# OpenBook_Reader_Schematic_Final.net
KiCad netlist of a schematic drawn in EAGLE
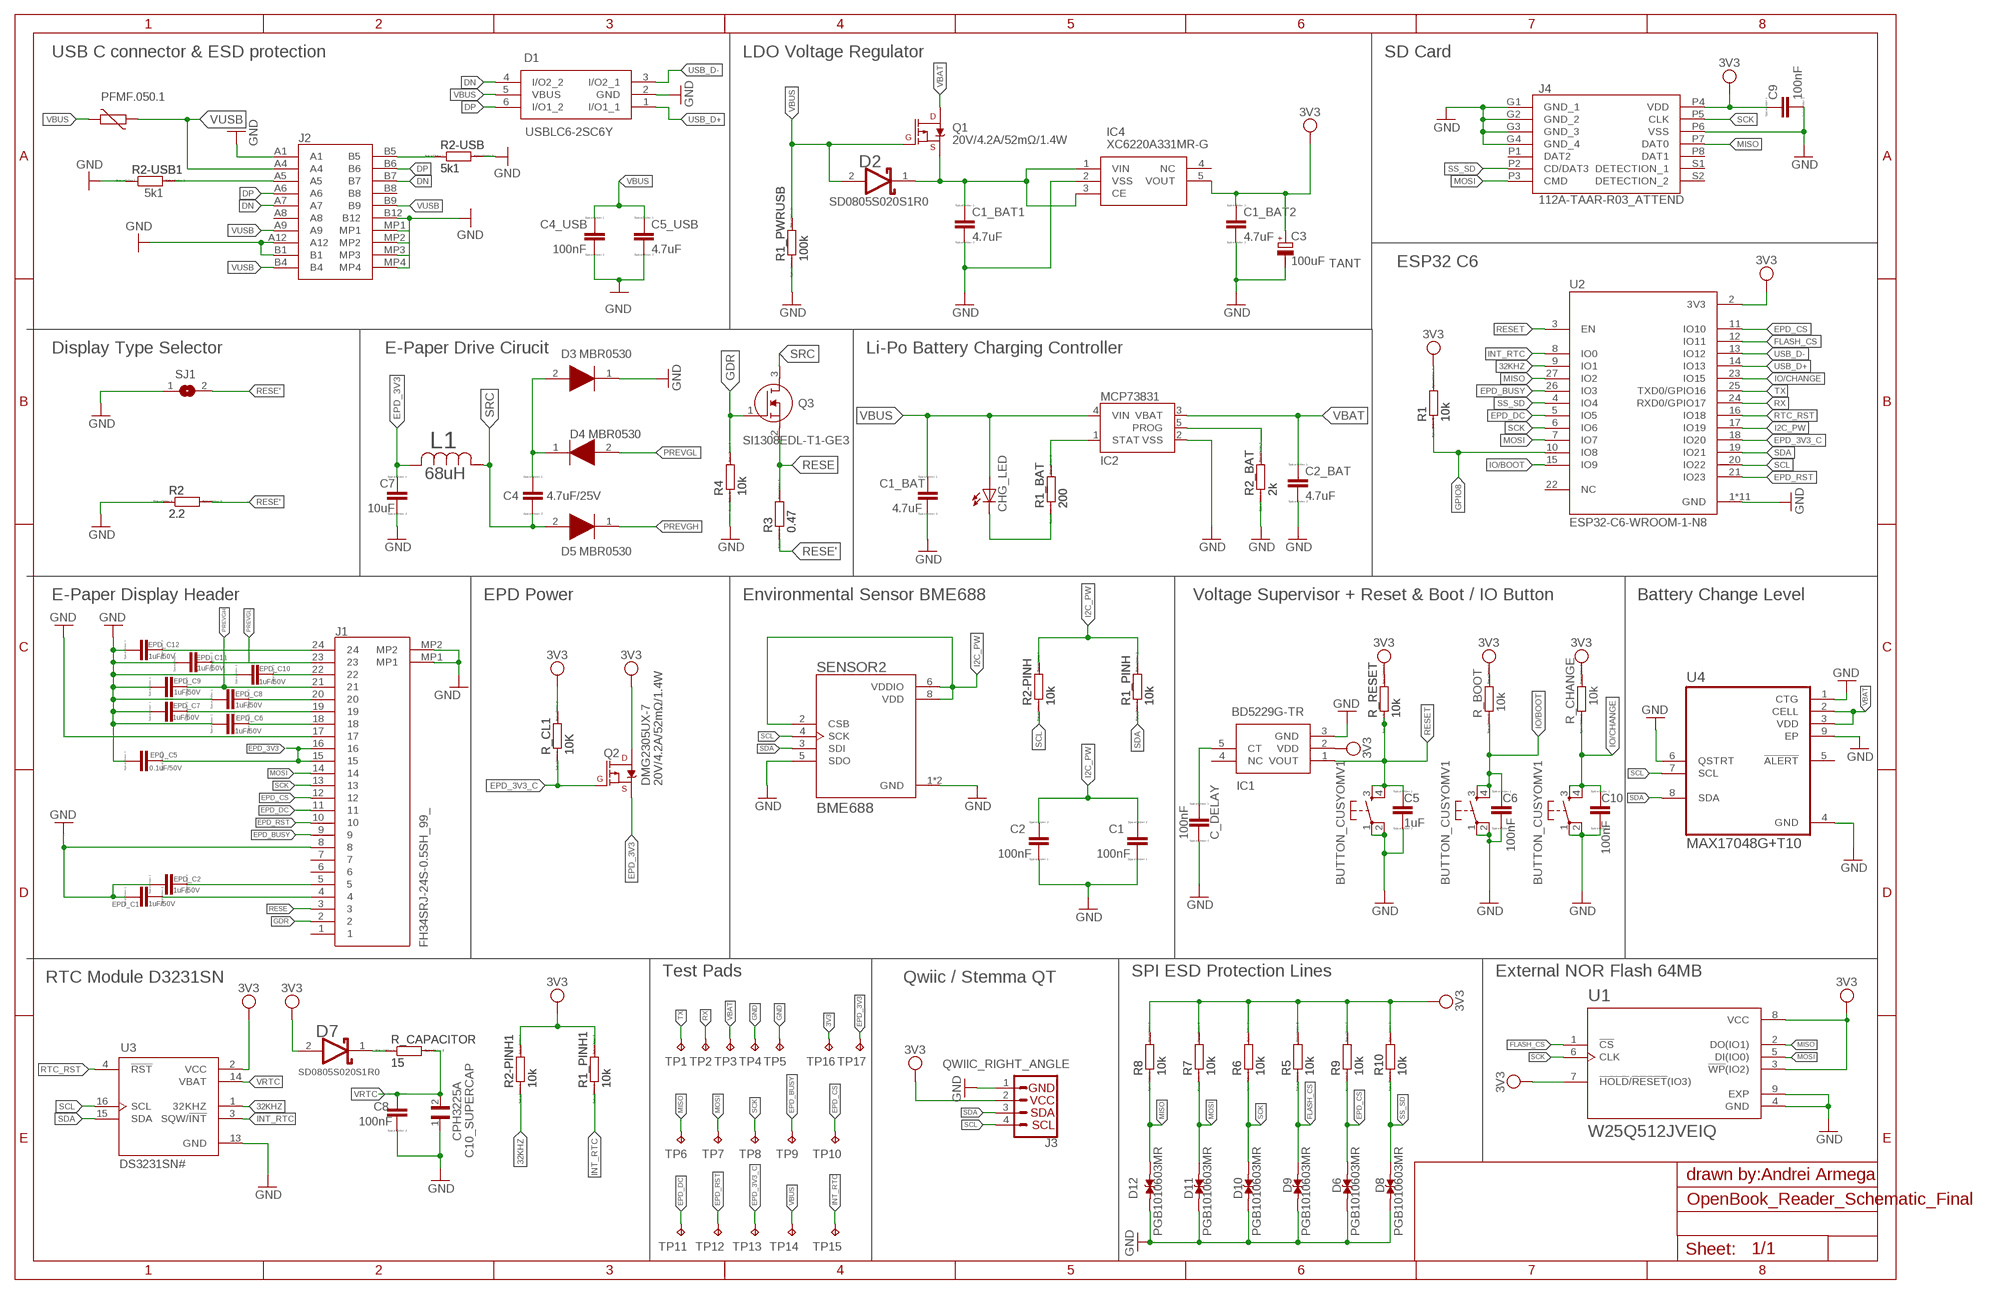
[diagram p0: schematic, sheet 1]

(export (version "E")
  (design (tool "Eeschema 10.0.6"))
  (components
    (comp (ref "BUT1")
      (value "BUTTON_CUSYOMV1")
      (footprint "eagle-import:MYBUTTON")
      (libsource (lib "eagle-import") (part "BUTTON_CUSYOMV1"))
    )
    (comp (ref "BUT2")
      (value "BUTTON_CUSYOMV1")
      (footprint "eagle-import:MYBUTTON")
      (libsource (lib "eagle-import") (part "BUTTON_CUSYOMV1"))
    )
    (comp (ref "BUT3")
      (value "BUTTON_CUSYOMV1")
      (footprint "eagle-import:MYBUTTON")
      (libsource (lib "eagle-import") (part "BUTTON_CUSYOMV1"))
    )
    (comp (ref "C1")
      (value "100nF")
      (footprint "eagle-import:ESP32_WROVER_EAGLE-LTSPICE_C0402")
      (libsource (lib "eagle-import") (part "ESP32_WROVER_EAGLE-LTSPICE_CC0402"))
    )
    (comp (ref "C1_BAT")
      (value "4.7uF")
      (footprint "eagle-import:ESP32_WROVER_EAGLE-LTSPICE_C0402")
      (libsource (lib "eagle-import") (part "ESP32_WROVER_EAGLE-LTSPICE_CC0402"))
    )
    (comp (ref "C1_BAT1")
      (value "4.7uF")
      (footprint "eagle-import:ESP32_WROVER_EAGLE-LTSPICE_C0402")
      (libsource (lib "eagle-import") (part "ESP32_WROVER_EAGLE-LTSPICE_CC0402"))
    )
    (comp (ref "C1_BAT2")
      (value "4.7uF")
      (footprint "eagle-import:ESP32_WROVER_EAGLE-LTSPICE_C0402")
      (libsource (lib "eagle-import") (part "ESP32_WROVER_EAGLE-LTSPICE_CC0402"))
    )
    (comp (ref "C2")
      (value "100nF")
      (footprint "eagle-import:ESP32_WROVER_EAGLE-LTSPICE_C0402")
      (libsource (lib "eagle-import") (part "ESP32_WROVER_EAGLE-LTSPICE_CC0402"))
    )
    (comp (ref "C2_BAT")
      (value "4.7uF")
      (footprint "eagle-import:ESP32_WROVER_EAGLE-LTSPICE_C0402")
      (libsource (lib "eagle-import") (part "ESP32_WROVER_EAGLE-LTSPICE_CC0402"))
    )
    (comp (ref "C3")
      (value "100uF")
      (footprint "eagle-import:RCL_CT3528")
      (libsource (lib "eagle-import") (part "RCL_CPOL-EUCT3528"))
    )
    (comp (ref "C4")
      (value "4.7uF/25V")
      (footprint "eagle-import:ESP32_WROVER_EAGLE-LTSPICE_C0402")
      (libsource (lib "eagle-import") (part "ESP32_WROVER_EAGLE-LTSPICE_CC0402"))
    )
    (comp (ref "C4_USB")
      (value "100nF")
      (footprint "eagle-import:ESP32_WROVER_EAGLE-LTSPICE_C0402")
      (libsource (lib "eagle-import") (part "ESP32_WROVER_EAGLE-LTSPICE_CC0402"))
    )
    (comp (ref "C5")
      (value "1uF")
      (footprint "eagle-import:ESP32_WROVER_EAGLE-LTSPICE_C0402")
      (libsource (lib "eagle-import") (part "EAGLE-LTSPICE_CC0402"))
    )
    (comp (ref "C5_USB")
      (value "4.7uF")
      (footprint "eagle-import:ESP32_WROVER_EAGLE-LTSPICE_C0402")
      (libsource (lib "eagle-import") (part "ESP32_WROVER_EAGLE-LTSPICE_CC0402"))
    )
    (comp (ref "C6")
      (value "100nF")
      (footprint "eagle-import:ESP32_WROVER_EAGLE-LTSPICE_C0402")
      (libsource (lib "eagle-import") (part "EAGLE-LTSPICE_CC0402"))
    )
    (comp (ref "C7")
      (value "10uF")
      (footprint "eagle-import:ESP32_WROVER_EAGLE-LTSPICE_C0402")
      (libsource (lib "eagle-import") (part "ESP32_WROVER_EAGLE-LTSPICE_CC0402"))
    )
    (comp (ref "C8")
      (value "100nF")
      (footprint "eagle-import:ESP32_WROVER_EAGLE-LTSPICE_C0402")
      (libsource (lib "eagle-import") (part "EAGLE-LTSPICE_CC0402"))
    )
    (comp (ref "C9")
      (value "100nF")
      (footprint "eagle-import:ESP32_WROVER_EAGLE-LTSPICE_C0402")
      (libsource (lib "eagle-import") (part "EAGLE-LTSPICE_CC0402"))
    )
    (comp (ref "C10")
      (value "100nF")
      (footprint "eagle-import:ESP32_WROVER_EAGLE-LTSPICE_C0402")
      (libsource (lib "eagle-import") (part "EAGLE-LTSPICE_CC0402"))
    )
    (comp (ref "C10_SUPERCAP")
      (value "CPH3225A")
      (footprint "eagle-import:CAPCP3225X100N")
      (fields (field (name "MF") "Seiko Instruments"))
      (libsource (lib "eagle-import") (part "CPH3225A"))
    )
    (comp (ref "CHG_LED")
      (value "ADAFRUIT_LEDCHIP-LED0603")
      (footprint "eagle-import:ADAFRUIT_CHIP-LED0603")
      (libsource (lib "eagle-import") (part "ADAFRUIT_LEDCHIP-LED0603"))
    )
    (comp (ref "C_DELAY")
      (value "100nF")
      (footprint "eagle-import:ESP32_WROVER_EAGLE-LTSPICE_C0402")
      (libsource (lib "eagle-import") (part "EAGLE-LTSPICE_CC0402"))
    )
    (comp (ref "D1")
      (value "USBLC6-2SC6Y")
      (footprint "eagle-import:SOT95P280X145-6N")
      (fields (field (name "MF") "STMicroelectronics"))
      (libsource (lib "eagle-import") (part "USBLC6-2SC6Y"))
    )
    (comp (ref "D2")
      (value "ESP32_WROVER_AVX---SD0805S020S1R0_AVX_SD0805S020S1R0_0_0AVX_SD0805S020S1R0_0_0")
      (footprint "eagle-import:ESP32_WROVER_AVX---SD0805S020S1R0_AVX_SD0805S020S1R0_0")
      (fields
        (field (name "DIGIKEY_PART_NUMBER") "478-7800-1-ND")
        (field (name "MF") "AVX")
        (field (name "MOUSER_PART_NUMBER") "581-SD0805S020S1R0")
      )
      (libsource (lib "eagle-import") (part "ESP32_WROVER_AVX---SD0805S020S1R0_AVX_SD0805S020S1R0_0_0AVX_SD0805S020S1R0_0_0"))
    )
    (comp (ref "D3")
      (value "MBR0530")
      (footprint "eagle-import:SOD3716X135N")
      (fields (field (name "MF") "ON Semiconductor"))
      (libsource (lib "eagle-import") (part "MBR0530"))
    )
    (comp (ref "D4")
      (value "MBR0530")
      (footprint "eagle-import:SOD3716X135N")
      (fields (field (name "MF") "ON Semiconductor"))
      (libsource (lib "eagle-import") (part "MBR0530"))
    )
    (comp (ref "D5")
      (value "MBR0530")
      (footprint "eagle-import:SOD3716X135N")
      (fields (field (name "MF") "ON Semiconductor"))
      (libsource (lib "eagle-import") (part "MBR0530"))
    )
    (comp (ref "D6")
      (value "PGB1010603MR")
      (footprint "eagle-import:DIOC1608X36N")
      (fields (field (name "MF") "Littelfuse Inc."))
      (libsource (lib "eagle-import") (part "PGB1010603MR"))
    )
    (comp (ref "D7")
      (value "ESP32_WROVER_AVX---SD0805S020S1R0_AVX_SD0805S020S1R0_0_0AVX_SD0805S020S1R0_0_0")
      (footprint "eagle-import:ESP32_WROVER_AVX---SD0805S020S1R0_AVX_SD0805S020S1R0_0")
      (fields
        (field (name "DIGIKEY_PART_NUMBER") "478-7800-1-ND")
        (field (name "MF") "AVX")
        (field (name "MOUSER_PART_NUMBER") "581-SD0805S020S1R0")
      )
      (libsource (lib "eagle-import") (part "ESP32_WROVER_AVX---SD0805S020S1R0_AVX_SD0805S020S1R0_0_0AVX_SD0805S020S1R0_0_0"))
    )
    (comp (ref "D8")
      (value "PGB1010603MR")
      (footprint "eagle-import:DIOC1608X36N")
      (fields (field (name "MF") "Littelfuse Inc."))
      (libsource (lib "eagle-import") (part "PGB1010603MR"))
    )
    (comp (ref "D9")
      (value "PGB1010603MR")
      (footprint "eagle-import:DIOC1608X36N")
      (fields (field (name "MF") "Littelfuse Inc."))
      (libsource (lib "eagle-import") (part "PGB1010603MR"))
    )
    (comp (ref "D10")
      (value "PGB1010603MR")
      (footprint "eagle-import:DIOC1608X36N")
      (fields (field (name "MF") "Littelfuse Inc."))
      (libsource (lib "eagle-import") (part "PGB1010603MR"))
    )
    (comp (ref "D11")
      (value "PGB1010603MR")
      (footprint "eagle-import:DIOC1608X36N")
      (fields (field (name "MF") "Littelfuse Inc."))
      (libsource (lib "eagle-import") (part "PGB1010603MR"))
    )
    (comp (ref "D12")
      (value "PGB1010603MR")
      (footprint "eagle-import:DIOC1608X36N")
      (fields (field (name "MF") "Littelfuse Inc."))
      (libsource (lib "eagle-import") (part "PGB1010603MR"))
    )
    (comp (ref "EPD_C1")
      (value "1uF/50V")
      (footprint "eagle-import:ESP32_WROVER_EAGLE-LTSPICE_C0402")
      (libsource (lib "eagle-import") (part "ESP32_WROVER_EAGLE-LTSPICE_CC0402"))
    )
    (comp (ref "EPD_C2")
      (value "1uF/50V")
      (footprint "eagle-import:ESP32_WROVER_EAGLE-LTSPICE_C0402")
      (libsource (lib "eagle-import") (part "ESP32_WROVER_EAGLE-LTSPICE_CC0402"))
    )
    (comp (ref "EPD_C5")
      (value "0.1uF/50V")
      (footprint "eagle-import:ESP32_WROVER_EAGLE-LTSPICE_C0402")
      (libsource (lib "eagle-import") (part "ESP32_WROVER_EAGLE-LTSPICE_CC0402"))
    )
    (comp (ref "EPD_C6")
      (value "1uF/50V")
      (footprint "eagle-import:ESP32_WROVER_EAGLE-LTSPICE_C0402")
      (libsource (lib "eagle-import") (part "ESP32_WROVER_EAGLE-LTSPICE_CC0402"))
    )
    (comp (ref "EPD_C7")
      (value "1uF/50V")
      (footprint "eagle-import:ESP32_WROVER_EAGLE-LTSPICE_C0402")
      (libsource (lib "eagle-import") (part "ESP32_WROVER_EAGLE-LTSPICE_CC0402"))
    )
    (comp (ref "EPD_C8")
      (value "1uF/50V")
      (footprint "eagle-import:ESP32_WROVER_EAGLE-LTSPICE_C0402")
      (libsource (lib "eagle-import") (part "ESP32_WROVER_EAGLE-LTSPICE_CC0402"))
    )
    (comp (ref "EPD_C9")
      (value "1uF/50V")
      (footprint "eagle-import:ESP32_WROVER_EAGLE-LTSPICE_C0402")
      (libsource (lib "eagle-import") (part "ESP32_WROVER_EAGLE-LTSPICE_CC0402"))
    )
    (comp (ref "EPD_C10")
      (value "1uF/50V")
      (footprint "eagle-import:ESP32_WROVER_EAGLE-LTSPICE_C0402")
      (libsource (lib "eagle-import") (part "ESP32_WROVER_EAGLE-LTSPICE_CC0402"))
    )
    (comp (ref "EPD_C11")
      (value "1uF/50V")
      (footprint "eagle-import:ESP32_WROVER_EAGLE-LTSPICE_C0402")
      (libsource (lib "eagle-import") (part "ESP32_WROVER_EAGLE-LTSPICE_CC0402"))
    )
    (comp (ref "EPD_C12")
      (value "1uF/50V")
      (footprint "eagle-import:ESP32_WROVER_EAGLE-LTSPICE_C0402")
      (libsource (lib "eagle-import") (part "ESP32_WROVER_EAGLE-LTSPICE_CC0402"))
    )
    (comp (ref "IC1")
      (value "BD5229G-TR")
      (footprint "eagle-import:SOT95P280X125-5N")
      (fields (field (name "MOUSER_PART_NUMBER") "755-BD5229G-TR"))
      (libsource (lib "eagle-import") (part "BD5229G-TR"))
    )
    (comp (ref "IC4")
      (value "XC6220A331MR-G")
      (footprint "eagle-import:SOT95P280X120-5N")
      (fields (field (name "MOUSER_PART_NUMBER") "865-XC6220A331MR-G"))
      (libsource (lib "eagle-import") (part "XC6220A331MR-G"))
    )
    (comp (ref "J1")
      (value "FH34SRJ-24S-0.5SH_99_")
      (footprint "eagle-import:FH34SRJ24S05SH99")
      (fields
        (field (name "MANUFACTURER_PART_NUMBER") "FH34SRJ-24S-0.5SH(99)")
        (field (name "MOUSER_PART_NUMBER") "798-FH34SRJ24S05SH99")
      )
      (libsource (lib "eagle-import") (part "FH34SRJ-24S-0.5SH_99_"))
    )
    (comp (ref "J2")
      (value "SAMACSYS_PARTS_USB4110-GF-A")
      (footprint "eagle-import:SAMACSYS_PARTS_USB4110GFA")
      (fields
        (field (name "MANUFACTURER_PART_NUMBER") "USB4110-GF-A")
        (field (name "MOUSER_PART_NUMBER") "640-USB4110-GF-A")
      )
      (libsource (lib "eagle-import") (part "SAMACSYS_PARTS_USB4110-GF-A"))
    )
    (comp (ref "J3")
      (value "QWIIC_RIGHT_ANGLE")
      (footprint "eagle-import:JST04_1MM_RA")
      (libsource (lib "eagle-import") (part "QWIIC_CONNECTORJS-1MM"))
    )
    (comp (ref "J4")
      (value "112A-TAAR-R03_ATTEND")
      (footprint "eagle-import:112ATAARR03ATTEND")
      (fields (field (name "MANUFACTURER_PART_NUMBER") "112A-TAAR-R03 ATTEND"))
      (libsource (lib "eagle-import") (part "112A-TAAR-R03_ATTEND"))
    )
    (comp (ref "L1")
      (value "68uH")
      (footprint "eagle-import:IND_4828-WE-TPC_WRE")
      (fields
        (field (name "MANUFACTURER_PART_NUMBER") "744043680")
        (field (name "COPYRIGHT") "Copyright (C) 2024 Ultra Librarian. All rights reserved.")
      )
      (libsource (lib "eagle-import") (part "744043680IND_4828-WE-TPC_WRE"))
    )
    (comp (ref "MCP73831")
      (value "ESP32_WROVER_SPARKFUN-IC-POWER_MCP73831")
      (footprint "eagle-import:ESP32_WROVER_SPARKFUN-IC-POWER_SOT23-5")
      (libsource (lib "eagle-import") (part "ESP32_WROVER_SPARKFUN-IC-POWER_MCP73831"))
    )
    (comp (ref "PFMF.050.1")
      (value "ESP32C6_VARISTORCN1812")
      (footprint "eagle-import:ESP32C6_VARISTOR_CT_CN1812")
      (libsource (lib "eagle-import") (part "ESP32C6_VARISTORCN1812"))
    )
    (comp (ref "Q1")
      (value "20V/4.2A/52mΩ/1.4W")
      (footprint "eagle-import:ESP32_WROVER_SPARKFUN-DISCRETESEMI_SOT23-3")
      (libsource (lib "eagle-import") (part "ESP32_WROVER_SPARKFUN-DISCRETESEMI_MOSFET_PCH-DMG2305UX-7"))
    )
    (comp (ref "Q2")
      (value "20V/4.2A/52mΩ/1.4W")
      (footprint "eagle-import:ESP32_WROVER_SPARKFUN-DISCRETESEMI_SOT23-3")
      (libsource (lib "eagle-import") (part "ESP32_WROVER_SPARKFUN-DISCRETESEMI_MOSFET_PCH-DMG2305UX-7"))
    )
    (comp (ref "Q3")
      (value "SI1308EDL-T1-GE3")
      (footprint "eagle-import:SOT65P210X110-3N")
      (fields (field (name "MF") "Vishay Siliconix"))
      (libsource (lib "eagle-import") (part "SI1308EDL-T1-GE3"))
    )
    (comp (ref "R1")
      (value "10k")
      (footprint "eagle-import:ESP32_WROVER_EAGLE-LTSPICE_R0402")
      (libsource (lib "eagle-import") (part "ESP32_WROVER_EAGLE-LTSPICE_RR0402"))
    )
    (comp (ref "R1_BAT")
      (value "200")
      (footprint "eagle-import:ESP32_WROVER_EAGLE-LTSPICE_R0402")
      (libsource (lib "eagle-import") (part "ESP32_WROVER_EAGLE-LTSPICE_RR0402"))
    )
    (comp (ref "R1_PINH")
      (value "10k")
      (footprint "eagle-import:ESP32_WROVER_EAGLE-LTSPICE_R0402")
      (libsource (lib "eagle-import") (part "ESP32_WROVER_EAGLE-LTSPICE_RR0402"))
    )
    (comp (ref "R1_PINH1")
      (value "10k")
      (footprint "eagle-import:ESP32_WROVER_EAGLE-LTSPICE_R0402")
      (libsource (lib "eagle-import") (part "ESP32_WROVER_EAGLE-LTSPICE_RR0402"))
    )
    (comp (ref "R1_PWRUSB")
      (value "100k")
      (footprint "eagle-import:ESP32_WROVER_EAGLE-LTSPICE_R0402")
      (libsource (lib "eagle-import") (part "ESP32_WROVER_EAGLE-LTSPICE_RR0402"))
    )
    (comp (ref "R2")
      (value "2.2")
      (footprint "eagle-import:ESP32_WROVER_EAGLE-LTSPICE_R0402")
      (libsource (lib "eagle-import") (part "ESP32_WROVER_EAGLE-LTSPICE_RR0402"))
    )
    (comp (ref "R2-PINH")
      (value "10k")
      (footprint "eagle-import:ESP32_WROVER_EAGLE-LTSPICE_R0402")
      (libsource (lib "eagle-import") (part "ESP32_WROVER_EAGLE-LTSPICE_RR0402"))
    )
    (comp (ref "R2-PINH1")
      (value "10k")
      (footprint "eagle-import:ESP32_WROVER_EAGLE-LTSPICE_R0402")
      (libsource (lib "eagle-import") (part "ESP32_WROVER_EAGLE-LTSPICE_RR0402"))
    )
    (comp (ref "R2-USB")
      (value "5k1")
      (footprint "eagle-import:ESP32_WROVER_EAGLE-LTSPICE_R0402")
      (libsource (lib "eagle-import") (part "ESP32_WROVER_EAGLE-LTSPICE_RR0402"))
    )
    (comp (ref "R2-USB1")
      (value "5k1")
      (footprint "eagle-import:ESP32_WROVER_EAGLE-LTSPICE_R0402")
      (libsource (lib "eagle-import") (part "ESP32_WROVER_EAGLE-LTSPICE_RR0402"))
    )
    (comp (ref "R2_BAT")
      (value "2k")
      (footprint "eagle-import:ESP32_WROVER_EAGLE-LTSPICE_R0402")
      (libsource (lib "eagle-import") (part "ESP32_WROVER_EAGLE-LTSPICE_RR0402"))
    )
    (comp (ref "R3")
      (value "0.47")
      (footprint "eagle-import:ESP32_WROVER_EAGLE-LTSPICE_R0402")
      (libsource (lib "eagle-import") (part "ESP32_WROVER_EAGLE-LTSPICE_RR0402"))
    )
    (comp (ref "R4")
      (value "10k")
      (footprint "eagle-import:ESP32_WROVER_EAGLE-LTSPICE_R0402")
      (libsource (lib "eagle-import") (part "ESP32_WROVER_EAGLE-LTSPICE_RR0402"))
    )
    (comp (ref "R5")
      (value "10k")
      (footprint "eagle-import:ESP32_WROVER_EAGLE-LTSPICE_R0402")
      (libsource (lib "eagle-import") (part "ESP32_WROVER_EAGLE-LTSPICE_RR0402"))
    )
    (comp (ref "R6")
      (value "10k")
      (footprint "eagle-import:ESP32_WROVER_EAGLE-LTSPICE_R0402")
      (libsource (lib "eagle-import") (part "ESP32_WROVER_EAGLE-LTSPICE_RR0402"))
    )
    (comp (ref "R7")
      (value "10k")
      (footprint "eagle-import:ESP32_WROVER_EAGLE-LTSPICE_R0402")
      (libsource (lib "eagle-import") (part "ESP32_WROVER_EAGLE-LTSPICE_RR0402"))
    )
    (comp (ref "R8")
      (value "10k")
      (footprint "eagle-import:ESP32_WROVER_EAGLE-LTSPICE_R0402")
      (libsource (lib "eagle-import") (part "ESP32_WROVER_EAGLE-LTSPICE_RR0402"))
    )
    (comp (ref "R9")
      (value "10k")
      (footprint "eagle-import:ESP32_WROVER_EAGLE-LTSPICE_R0402")
      (libsource (lib "eagle-import") (part "ESP32_WROVER_EAGLE-LTSPICE_RR0402"))
    )
    (comp (ref "R10")
      (value "10k")
      (footprint "eagle-import:ESP32_WROVER_EAGLE-LTSPICE_R0402")
      (libsource (lib "eagle-import") (part "ESP32_WROVER_EAGLE-LTSPICE_RR0402"))
    )
    (comp (ref "R_BOOT")
      (value "10k")
      (footprint "eagle-import:ESP32_WROVER_EAGLE-LTSPICE_R0402")
      (libsource (lib "eagle-import") (part "ESP32_WROVER_EAGLE-LTSPICE_RR0402"))
    )
    (comp (ref "R_CAPACITOR")
      (value "15")
      (footprint "eagle-import:ESP32_WROVER_EAGLE-LTSPICE_R0402")
      (libsource (lib "eagle-import") (part "ESP32_WROVER_EAGLE-LTSPICE_RR0402"))
    )
    (comp (ref "R_CHANGE")
      (value "10k")
      (footprint "eagle-import:ESP32_WROVER_EAGLE-LTSPICE_R0402")
      (libsource (lib "eagle-import") (part "ESP32_WROVER_EAGLE-LTSPICE_RR0402"))
    )
    (comp (ref "R_CL1")
      (value "10K")
      (footprint "eagle-import:ESP32_WROVER_EAGLE-LTSPICE_R0402")
      (libsource (lib "eagle-import") (part "ESP32_WROVER_EAGLE-LTSPICE_RR0402"))
    )
    (comp (ref "R_RESET")
      (value "10k")
      (footprint "eagle-import:ESP32_WROVER_EAGLE-LTSPICE_R0402")
      (libsource (lib "eagle-import") (part "ESP32_WROVER_EAGLE-LTSPICE_RR0402"))
    )
    (comp (ref "SENSOR2")
      (value "ESP32_WROVER_BME680_BME680")
      (footprint "eagle-import:ESP32_WROVER_BME680_PSON80P300X300X100-8N")
      (fields (field (name "MF") "Bosch Sensortec") (field (name "MP") "BME680"))
      (libsource (lib "eagle-import") (part "ESP32_WROVER_BME680_BME680"))
    )
    (comp (ref "SJ1") (value "SJ") (footprint "eagle-import:SJ") (libsource (lib "eagle-import") (part "SJ")))
    (comp (ref "TP1")
      (value "TPTP20R")
      (footprint "eagle-import:TP20R")
      (libsource (lib "eagle-import") (part "TPTP20R"))
    )
    (comp (ref "TP2")
      (value "TPTP20R")
      (footprint "eagle-import:TP20R")
      (libsource (lib "eagle-import") (part "TPTP20R"))
    )
    (comp (ref "TP3")
      (value "TPTP20R")
      (footprint "eagle-import:TP20R")
      (libsource (lib "eagle-import") (part "TPTP20R"))
    )
    (comp (ref "TP4")
      (value "TPTP20R")
      (footprint "eagle-import:TP20R")
      (libsource (lib "eagle-import") (part "TPTP20R"))
    )
    (comp (ref "TP5")
      (value "TPTP20R")
      (footprint "eagle-import:TP20R")
      (libsource (lib "eagle-import") (part "TPTP20R"))
    )
    (comp (ref "TP6")
      (value "TPTP20R")
      (footprint "eagle-import:TP20R")
      (libsource (lib "eagle-import") (part "TPTP20R"))
    )
    (comp (ref "TP7")
      (value "TPTP20R")
      (footprint "eagle-import:TP20R")
      (libsource (lib "eagle-import") (part "TPTP20R"))
    )
    (comp (ref "TP8")
      (value "TPTP20R")
      (footprint "eagle-import:TP20R")
      (libsource (lib "eagle-import") (part "TPTP20R"))
    )
    (comp (ref "TP9")
      (value "TPTP20R")
      (footprint "eagle-import:TP20R")
      (libsource (lib "eagle-import") (part "TPTP20R"))
    )
    (comp (ref "TP10")
      (value "TPTP20R")
      (footprint "eagle-import:TP20R")
      (libsource (lib "eagle-import") (part "TPTP20R"))
    )
    (comp (ref "TP11")
      (value "TPTP20R")
      (footprint "eagle-import:TP20R")
      (libsource (lib "eagle-import") (part "TPTP20R"))
    )
    (comp (ref "TP12")
      (value "TPTP20R")
      (footprint "eagle-import:TP20R")
      (libsource (lib "eagle-import") (part "TPTP20R"))
    )
    (comp (ref "TP13")
      (value "TPTP20R")
      (footprint "eagle-import:TP20R")
      (libsource (lib "eagle-import") (part "TPTP20R"))
    )
    (comp (ref "TP14")
      (value "TPTP20R")
      (footprint "eagle-import:TP20R")
      (libsource (lib "eagle-import") (part "TPTP20R"))
    )
    (comp (ref "TP15")
      (value "TPTP20R")
      (footprint "eagle-import:TP20R")
      (libsource (lib "eagle-import") (part "TPTP20R"))
    )
    (comp (ref "TP16")
      (value "TPTP20R")
      (footprint "eagle-import:TP20R")
      (libsource (lib "eagle-import") (part "TPTP20R"))
    )
    (comp (ref "TP17")
      (value "TPTP20R")
      (footprint "eagle-import:TP20R")
      (libsource (lib "eagle-import") (part "TPTP20R"))
    )
    (comp (ref "U1")
      (value "W25Q512JVEIQ")
      (footprint "eagle-import:SON127P600X800X80-9N")
      (fields (field (name "MF") "Winbond Electronics"))
      (libsource (lib "eagle-import") (part "W25Q512JVEIQ"))
    )
    (comp (ref "U2")
      (value "ESP32-C6-WROOM-1-N8")
      (footprint "eagle-import:XCVR_ESP32-C6-WROOM-1-N8")
      (fields (field (name "MF") "Espressif Systems"))
      (libsource (lib "eagle-import") (part "ESP32-C6-WROOM-1-N8"))
    )
    (comp (ref "U3")
      (value "DS3231SN#")
      (footprint "eagle-import:SOIC127P1032X265-16N")
      (fields (field (name "MF") "Analog Devices"))
      (libsource (lib "eagle-import") (part "DS3231SN#"))
    )
    (comp (ref "U4")
      (value "MAX17048G+T10")
      (footprint "eagle-import:SON50P200X200X80-9N")
      (fields (field (name "MF") "Analog Devices"))
      (libsource (lib "eagle-import") (part "MAX17048G+T10"))
    )
  )
  (nets
    (net (code "1") (name "3V3") (class "Default")
      (node (ref "C1_BAT2") (pin "1") (pinfunction "1_1") (pintype "passive"))
      (node (ref "C3") (pin "+") (pinfunction "+_+") (pintype "passive"))
      (node (ref "C9") (pin "1") (pinfunction "1_1") (pintype "passive"))
      (node (ref "D7") (pin "2") (pinfunction "ANODE_2") (pintype "bidirectional"))
      (node (ref "IC1") (pin "2") (pinfunction "VDD_2") (pintype "bidirectional"))
      (node (ref "IC4") (pin "5") (pinfunction "VOUT_5") (pintype "bidirectional"))
      (node (ref "J3") (pin "2") (pinfunction "2_2") (pintype "power_in"))
      (node (ref "J4") (pin "P4") (pinfunction "VDD_P4") (pintype "bidirectional"))
      (node (ref "Q2") (pin "3") (pinfunction "D_3") (pintype "bidirectional"))
      (node (ref "R1") (pin "2") (pinfunction "2_2") (pintype "passive"))
      (node (ref "R10") (pin "2") (pinfunction "2_2") (pintype "passive"))
      (node (ref "R1_PINH1") (pin "2") (pinfunction "2_2") (pintype "passive"))
      (node (ref "R2-PINH1") (pin "2") (pinfunction "2_2") (pintype "passive"))
      (node (ref "R5") (pin "2") (pinfunction "2_2") (pintype "passive"))
      (node (ref "R6") (pin "2") (pinfunction "2_2") (pintype "passive"))
      (node (ref "R7") (pin "2") (pinfunction "2_2") (pintype "passive"))
      (node (ref "R8") (pin "2") (pinfunction "2_2") (pintype "passive"))
      (node (ref "R9") (pin "2") (pinfunction "2_2") (pintype "passive"))
      (node (ref "R_BOOT") (pin "2") (pinfunction "2_2") (pintype "passive"))
      (node (ref "R_CHANGE") (pin "2") (pinfunction "2_2") (pintype "passive"))
      (node (ref "R_CL1") (pin "2") (pinfunction "2_2") (pintype "passive"))
      (node (ref "R_RESET") (pin "2") (pinfunction "2_2") (pintype "passive"))
      (node (ref "TP16") (pin "TP") (pinfunction "TP_TP") (pintype "input"))
      (node (ref "U1") (pin "3") (pinfunction "~{WP}(IO2)_3") (pintype "bidirectional"))
      (node (ref "U1") (pin "7") (pinfunction "~{HOLD}/~{RESET}(IO3)_7") (pintype "bidirectional"))
      (node (ref "U1") (pin "8") (pinfunction "VCC_8") (pintype "power_in"))
      (node (ref "U2") (pin "2") (pinfunction "3V3_2") (pintype "power_in"))
      (node (ref "U3") (pin "2") (pinfunction "VCC_2") (pintype "power_in"))
    )
    (net (code "2") (name "32KHZ") (class "Default")
      (node (ref "R2-PINH1") (pin "1") (pinfunction "1_1") (pintype "passive"))
      (node (ref "U2") (pin "9") (pinfunction "IO1_9") (pintype "bidirectional"))
      (node (ref "U3") (pin "1") (pinfunction "32KHZ_1") (pintype "output"))
    )
    (net (code "3") (name "DN") (class "Default")
      (node (ref "D1") (pin "4") (pinfunction "I/O2_2_4") (pintype "bidirectional"))
      (node (ref "J2") (pin "A7") (pinfunction "A7_A7") (pintype "bidirectional"))
      (node (ref "J2") (pin "B7") (pinfunction "B7_B7") (pintype "bidirectional"))
    )
    (net (code "4") (name "DP") (class "Default")
      (node (ref "D1") (pin "6") (pinfunction "I/O1_2_6") (pintype "bidirectional"))
      (node (ref "J2") (pin "A6") (pinfunction "A6_A6") (pintype "bidirectional"))
      (node (ref "J2") (pin "B6") (pinfunction "B6_B6") (pintype "bidirectional"))
    )
    (net (code "5") (name "EPD_3V3") (class "Default")
      (node (ref "C7") (pin "1") (pinfunction "1_1") (pintype "passive"))
      (node (ref "EPD_C5") (pin "2") (pinfunction "2_2") (pintype "passive"))
      (node (ref "J1") (pin "15") (pinfunction "15_15") (pintype "bidirectional"))
      (node (ref "J1") (pin "16") (pinfunction "16_16") (pintype "bidirectional"))
      (node (ref "L1") (pin "2") (pinfunction "2_2") (pintype "passive"))
      (node (ref "Q2") (pin "2") (pinfunction "S_2") (pintype "bidirectional"))
      (node (ref "TP17") (pin "TP") (pinfunction "TP_TP") (pintype "input"))
    )
    (net (code "6") (name "EPD_3V3_C") (class "Default")
      (node (ref "Q2") (pin "1") (pinfunction "G_1") (pintype "bidirectional"))
      (node (ref "R_CL1") (pin "1") (pinfunction "1_1") (pintype "passive"))
      (node (ref "TP13") (pin "TP") (pinfunction "TP_TP") (pintype "input"))
      (node (ref "U2") (pin "18") (pinfunction "IO20_18") (pintype "bidirectional"))
    )
    (net (code "7") (name "EPD_BUSY") (class "Default")
      (node (ref "J1") (pin "9") (pinfunction "9_9") (pintype "bidirectional"))
      (node (ref "TP9") (pin "TP") (pinfunction "TP_TP") (pintype "input"))
      (node (ref "U2") (pin "26") (pinfunction "IO3_26") (pintype "bidirectional"))
    )
    (net (code "8") (name "EPD_CS") (class "Default")
      (node (ref "D6") (pin "2") (pinfunction "2_2") (pintype "passive"))
      (node (ref "J1") (pin "12") (pinfunction "12_12") (pintype "bidirectional"))
      (node (ref "R9") (pin "1") (pinfunction "1_1") (pintype "passive"))
      (node (ref "TP10") (pin "TP") (pinfunction "TP_TP") (pintype "input"))
      (node (ref "U2") (pin "11") (pinfunction "IO10_11") (pintype "bidirectional"))
    )
    (net (code "9") (name "EPD_DC") (class "Default")
      (node (ref "J1") (pin "11") (pinfunction "11_11") (pintype "bidirectional"))
      (node (ref "TP11") (pin "TP") (pinfunction "TP_TP") (pintype "input"))
      (node (ref "U2") (pin "5") (pinfunction "IO5_5") (pintype "bidirectional"))
    )
    (net (code "10") (name "EPD_RST") (class "Default")
      (node (ref "J1") (pin "10") (pinfunction "10_10") (pintype "bidirectional"))
      (node (ref "TP12") (pin "TP") (pinfunction "TP_TP") (pintype "input"))
      (node (ref "U2") (pin "21") (pinfunction "IO23_21") (pintype "bidirectional"))
    )
    (net (code "11") (name "FLASH_CS") (class "Default")
      (node (ref "D9") (pin "2") (pinfunction "2_2") (pintype "passive"))
      (node (ref "R5") (pin "1") (pinfunction "1_1") (pintype "passive"))
      (node (ref "U1") (pin "1") (pinfunction "~{CS}_1") (pintype "input"))
      (node (ref "U2") (pin "12") (pinfunction "IO11_12") (pintype "bidirectional"))
    )
    (net (code "12") (name "GDR") (class "Default")
      (node (ref "J1") (pin "2") (pinfunction "2_2") (pintype "bidirectional"))
      (node (ref "Q3") (pin "1") (pinfunction "G_1") (pintype "bidirectional"))
      (node (ref "R4") (pin "2") (pinfunction "2_2") (pintype "passive"))
    )
    (net (code "13") (name "GND") (class "Default")
      (node (ref "BUT1") (pin "1") (pinfunction "1_1") (pintype "passive"))
      (node (ref "BUT1") (pin "2") (pinfunction "2_2") (pintype "passive"))
      (node (ref "BUT2") (pin "1") (pinfunction "1_1") (pintype "passive"))
      (node (ref "BUT2") (pin "2") (pinfunction "2_2") (pintype "passive"))
      (node (ref "BUT3") (pin "1") (pinfunction "1_1") (pintype "passive"))
      (node (ref "BUT3") (pin "2") (pinfunction "2_2") (pintype "passive"))
      (node (ref "C1") (pin "1") (pinfunction "1_1") (pintype "passive"))
      (node (ref "C10") (pin "2") (pinfunction "2_2") (pintype "passive"))
      (node (ref "C10_SUPERCAP") (pin "1") (pinfunction "1_1") (pintype "passive"))
      (node (ref "C1_BAT") (pin "2") (pinfunction "2_2") (pintype "passive"))
      (node (ref "C1_BAT1") (pin "2") (pinfunction "2_2") (pintype "passive"))
      (node (ref "C1_BAT2") (pin "2") (pinfunction "2_2") (pintype "passive"))
      (node (ref "C2") (pin "1") (pinfunction "1_1") (pintype "passive"))
      (node (ref "C2_BAT") (pin "2") (pinfunction "2_2") (pintype "passive"))
      (node (ref "C3") (pin "-") (pinfunction "-_-") (pintype "passive"))
      (node (ref "C4_USB") (pin "2") (pinfunction "2_2") (pintype "passive"))
      (node (ref "C5") (pin "2") (pinfunction "2_2") (pintype "passive"))
      (node (ref "C5_USB") (pin "2") (pinfunction "2_2") (pintype "passive"))
      (node (ref "C6") (pin "2") (pinfunction "2_2") (pintype "passive"))
      (node (ref "C7") (pin "2") (pinfunction "2_2") (pintype "passive"))
      (node (ref "C8") (pin "2") (pinfunction "2_2") (pintype "passive"))
      (node (ref "C9") (pin "2") (pinfunction "2_2") (pintype "passive"))
      (node (ref "C_DELAY") (pin "2") (pinfunction "2_2") (pintype "passive"))
      (node (ref "D1") (pin "2") (pinfunction "GND_2") (pintype "bidirectional"))
      (node (ref "D10") (pin "1") (pinfunction "1_1") (pintype "passive"))
      (node (ref "D11") (pin "1") (pinfunction "1_1") (pintype "passive"))
      (node (ref "D12") (pin "1") (pinfunction "1_1") (pintype "passive"))
      (node (ref "D3") (pin "1") (pinfunction "K_1") (pintype "bidirectional"))
      (node (ref "D6") (pin "1") (pinfunction "1_1") (pintype "passive"))
      (node (ref "D8") (pin "1") (pinfunction "1_1") (pintype "passive"))
      (node (ref "D9") (pin "1") (pinfunction "1_1") (pintype "passive"))
      (node (ref "EPD_C1") (pin "1") (pinfunction "1_1") (pintype "passive"))
      (node (ref "EPD_C10") (pin "1") (pinfunction "1_1") (pintype "passive"))
      (node (ref "EPD_C11") (pin "1") (pinfunction "1_1") (pintype "passive"))
      (node (ref "EPD_C12") (pin "1") (pinfunction "1_1") (pintype "passive"))
      (node (ref "EPD_C2") (pin "1") (pinfunction "1_1") (pintype "passive"))
      (node (ref "EPD_C5") (pin "1") (pinfunction "1_1") (pintype "passive"))
      (node (ref "EPD_C6") (pin "1") (pinfunction "1_1") (pintype "passive"))
      (node (ref "EPD_C7") (pin "1") (pinfunction "1_1") (pintype "passive"))
      (node (ref "EPD_C8") (pin "1") (pinfunction "1_1") (pintype "passive"))
      (node (ref "EPD_C9") (pin "1") (pinfunction "1_1") (pintype "passive"))
      (node (ref "IC1") (pin "3") (pinfunction "GND_3") (pintype "bidirectional"))
      (node (ref "IC4") (pin "2") (pinfunction "VSS_2") (pintype "bidirectional"))
      (node (ref "J1") (pin "17") (pinfunction "17_17") (pintype "bidirectional"))
      (node (ref "J1") (pin "8") (pinfunction "8_8") (pintype "bidirectional"))
      (node (ref "J1") (pin "MP1") (pinfunction "MP1_MP1") (pintype "bidirectional"))
      (node (ref "J1") (pin "MP2") (pinfunction "MP2_MP2") (pintype "bidirectional"))
      (node (ref "J2") (pin "A1") (pinfunction "A1_A1") (pintype "bidirectional"))
      (node (ref "J2") (pin "A12") (pinfunction "A12_A12") (pintype "bidirectional"))
      (node (ref "J2") (pin "B1") (pinfunction "B1_B1") (pintype "bidirectional"))
      (node (ref "J2") (pin "B12") (pinfunction "B12_B12") (pintype "bidirectional"))
      (node (ref "J2") (pin "MP1") (pinfunction "MP1_MP1") (pintype "bidirectional"))
      (node (ref "J2") (pin "MP2") (pinfunction "MP2_MP2") (pintype "bidirectional"))
      (node (ref "J2") (pin "MP3") (pinfunction "MP3_MP3") (pintype "bidirectional"))
      (node (ref "J2") (pin "MP4") (pinfunction "MP4_MP4") (pintype "bidirectional"))
      (node (ref "J3") (pin "1") (pinfunction "1_1") (pintype "power_in"))
      (node (ref "J4") (pin "G1") (pinfunction "GND_1_G1") (pintype "bidirectional"))
      (node (ref "J4") (pin "G2") (pinfunction "GND_2_G2") (pintype "bidirectional"))
      (node (ref "J4") (pin "G3") (pinfunction "GND_3_G3") (pintype "bidirectional"))
      (node (ref "J4") (pin "G4") (pinfunction "GND_4_G4") (pintype "bidirectional"))
      (node (ref "J4") (pin "P6") (pinfunction "VSS_P6") (pintype "bidirectional"))
      (node (ref "MCP73831") (pin "2") (pinfunction "VSS_2") (pintype "power_in"))
      (node (ref "R1_PWRUSB") (pin "1") (pinfunction "1_1") (pintype "passive"))
      (node (ref "R2") (pin "1") (pinfunction "1_1") (pintype "passive"))
      (node (ref "R2-USB") (pin "2") (pinfunction "2_2") (pintype "passive"))
      (node (ref "R2-USB1") (pin "1") (pinfunction "1_1") (pintype "passive"))
      (node (ref "R2_BAT") (pin "1") (pinfunction "1_1") (pintype "passive"))
      (node (ref "R4") (pin "1") (pinfunction "1_1") (pintype "passive"))
      (node (ref "SENSOR2") (pin "1") (pinfunction "GND_1") (pintype "power_in"))
      (node (ref "SENSOR2") (pin "5") (pinfunction "SDO_5") (pintype "bidirectional"))
      (node (ref "SENSOR2") (pin "7") (pinfunction "GND_7") (pintype "power_in"))
      (node (ref "SJ1") (pin "1") (pinfunction "1_1") (pintype "passive"))
      (node (ref "TP4") (pin "TP") (pinfunction "TP_TP") (pintype "input"))
      (node (ref "TP5") (pin "TP") (pinfunction "TP_TP") (pintype "input"))
      (node (ref "U1") (pin "4") (pinfunction "GND_4") (pintype "power_in"))
      (node (ref "U1") (pin "9") (pinfunction "EXP_9") (pintype "passive"))
      (node (ref "U2") (pin "1") (pinfunction "GND_1") (pintype "power_in"))
      (node (ref "U2") (pin "28") (pinfunction "GND_28") (pintype "power_in"))
      (node (ref "U2") (pin "29_1") (pinfunction "GND_29_1") (pintype "power_in"))
      (node (ref "U2") (pin "29_2") (pinfunction "GND_29_2") (pintype "power_in"))
      (node (ref "U2") (pin "29_3") (pinfunction "GND_29_3") (pintype "power_in"))
      (node (ref "U2") (pin "29_4") (pinfunction "GND_29_4") (pintype "power_in"))
      (node (ref "U2") (pin "29_5") (pinfunction "GND_29_5") (pintype "power_in"))
      (node (ref "U2") (pin "29_6") (pinfunction "GND_29_6") (pintype "power_in"))
      (node (ref "U2") (pin "29_7") (pinfunction "GND_29_7") (pintype "power_in"))
      (node (ref "U2") (pin "29_8") (pinfunction "GND_29_8") (pintype "power_in"))
      (node (ref "U2") (pin "29_9") (pinfunction "GND_29_9") (pintype "power_in"))
      (node (ref "U3") (pin "13") (pinfunction "GND_13") (pintype "power_in"))
      (node (ref "U4") (pin "1") (pinfunction "CTG_1") (pintype "power_in"))
      (node (ref "U4") (pin "4") (pinfunction "GND_4") (pintype "power_in"))
      (node (ref "U4") (pin "6") (pinfunction "QSTRT_6") (pintype "input"))
      (node (ref "U4") (pin "9") (pinfunction "EP_9") (pintype "power_in"))
    )
    (net (code "14") (name "GPIO8") (class "Default")
      (node (ref "R1") (pin "1") (pinfunction "1_1") (pintype "passive"))
      (node (ref "U2") (pin "10") (pinfunction "IO8_10") (pintype "bidirectional"))
    )
    (net (code "15") (name "I2C_PW") (class "Default")
      (node (ref "C1") (pin "2") (pinfunction "2_2") (pintype "passive"))
      (node (ref "C2") (pin "2") (pinfunction "2_2") (pintype "passive"))
      (node (ref "R1_PINH") (pin "2") (pinfunction "2_2") (pintype "passive"))
      (node (ref "R2-PINH") (pin "2") (pinfunction "2_2") (pintype "passive"))
      (node (ref "SENSOR2") (pin "2") (pinfunction "CSB_2") (pintype "input"))
      (node (ref "SENSOR2") (pin "6") (pinfunction "VDDIO_6") (pintype "power_in"))
      (node (ref "SENSOR2") (pin "8") (pinfunction "VDD_8") (pintype "power_in"))
      (node (ref "U2") (pin "17") (pinfunction "IO19_17") (pintype "bidirectional"))
    )
    (net (code "16") (name "INT_RTC") (class "Default")
      (node (ref "R1_PINH1") (pin "1") (pinfunction "1_1") (pintype "passive"))
      (node (ref "TP15") (pin "TP") (pinfunction "TP_TP") (pintype "input"))
      (node (ref "U2") (pin "8") (pinfunction "IO0_8") (pintype "bidirectional"))
      (node (ref "U3") (pin "3") (pinfunction "SQW/~{INT}_3") (pintype "output"))
    )
    (net (code "17") (name "IO{slash}BOOT") (class "Default")
      (node (ref "BUT2") (pin "3") (pinfunction "3_3") (pintype "passive"))
      (node (ref "BUT2") (pin "4") (pinfunction "4_4") (pintype "passive"))
      (node (ref "C6") (pin "1") (pinfunction "1_1") (pintype "passive"))
      (node (ref "R_BOOT") (pin "1") (pinfunction "1_1") (pintype "passive"))
      (node (ref "U2") (pin "15") (pinfunction "IO9_15") (pintype "bidirectional"))
    )
    (net (code "18") (name "IO{slash}CHANGE") (class "Default")
      (node (ref "BUT3") (pin "3") (pinfunction "3_3") (pintype "passive"))
      (node (ref "BUT3") (pin "4") (pinfunction "4_4") (pintype "passive"))
      (node (ref "C10") (pin "1") (pinfunction "1_1") (pintype "passive"))
      (node (ref "R_CHANGE") (pin "1") (pinfunction "1_1") (pintype "passive"))
      (node (ref "U2") (pin "23") (pinfunction "IO15_23") (pintype "bidirectional"))
    )
    (net (code "19") (name "MISO") (class "Default")
      (node (ref "D12") (pin "2") (pinfunction "2_2") (pintype "passive"))
      (node (ref "J4") (pin "P7") (pinfunction "DAT0_P7") (pintype "bidirectional"))
      (node (ref "R8") (pin "1") (pinfunction "1_1") (pintype "passive"))
      (node (ref "TP6") (pin "TP") (pinfunction "TP_TP") (pintype "input"))
      (node (ref "U1") (pin "2") (pinfunction "DO(IO1)_2") (pintype "bidirectional"))
      (node (ref "U2") (pin "27") (pinfunction "IO2_27") (pintype "bidirectional"))
    )
    (net (code "20") (name "MOSI") (class "Default")
      (node (ref "D11") (pin "2") (pinfunction "2_2") (pintype "passive"))
      (node (ref "J1") (pin "14") (pinfunction "14_14") (pintype "bidirectional"))
      (node (ref "J4") (pin "P3") (pinfunction "CMD_P3") (pintype "bidirectional"))
      (node (ref "R7") (pin "1") (pinfunction "1_1") (pintype "passive"))
      (node (ref "TP7") (pin "TP") (pinfunction "TP_TP") (pintype "input"))
      (node (ref "U1") (pin "5") (pinfunction "DI(IO0)_5") (pintype "bidirectional"))
      (node (ref "U2") (pin "7") (pinfunction "IO7_7") (pintype "bidirectional"))
    )
    (net (code "21") (name "Net-(CHG_LED-PadC)") (class "Default")
      (node (ref "CHG_LED") (pin "C") (pinfunction "C_C") (pintype "passive"))
      (node (ref "R1_BAT") (pin "1") (pinfunction "1_1") (pintype "passive"))
    )
    (net (code "22") (name "Net-(D2-CATHODE)") (class "Default")
      (node (ref "C1_BAT1") (pin "1") (pinfunction "1_1") (pintype "passive"))
      (node (ref "D2") (pin "1") (pinfunction "CATHODE_1") (pintype "bidirectional"))
      (node (ref "IC4") (pin "1") (pinfunction "VIN_1") (pintype "bidirectional"))
      (node (ref "IC4") (pin "3") (pinfunction "CE_3") (pintype "bidirectional"))
      (node (ref "Q1") (pin "2") (pinfunction "S_2") (pintype "bidirectional"))
    )
    (net (code "23") (name "Net-(D3-A)") (class "Default")
      (node (ref "C4") (pin "1") (pinfunction "1_1") (pintype "passive"))
      (node (ref "D3") (pin "2") (pinfunction "A_2") (pintype "bidirectional"))
      (node (ref "D4") (pin "1") (pinfunction "K_1") (pintype "bidirectional"))
    )
    (net (code "24") (name "Net-(D7-CATHODE)") (class "Default")
      (node (ref "D7") (pin "1") (pinfunction "CATHODE_1") (pintype "bidirectional"))
      (node (ref "R_CAPACITOR") (pin "1") (pinfunction "1_1") (pintype "passive"))
    )
    (net (code "25") (name "Net-(EPD_C1-Pad2)") (class "Default")
      (node (ref "EPD_C1") (pin "2") (pinfunction "2_2") (pintype "passive"))
      (node (ref "J1") (pin "4") (pinfunction "4_4") (pintype "bidirectional"))
    )
    (net (code "26") (name "Net-(EPD_C2-Pad2)") (class "Default")
      (node (ref "EPD_C2") (pin "2") (pinfunction "2_2") (pintype "passive"))
      (node (ref "J1") (pin "5") (pinfunction "5_5") (pintype "bidirectional"))
    )
    (net (code "27") (name "Net-(EPD_C6-Pad2)") (class "Default")
      (node (ref "EPD_C6") (pin "2") (pinfunction "2_2") (pintype "passive"))
      (node (ref "J1") (pin "18") (pinfunction "18_18") (pintype "bidirectional"))
    )
    (net (code "28") (name "Net-(EPD_C7-Pad2)") (class "Default")
      (node (ref "EPD_C7") (pin "2") (pinfunction "2_2") (pintype "passive"))
      (node (ref "J1") (pin "19") (pinfunction "19_19") (pintype "bidirectional"))
    )
    (net (code "29") (name "Net-(EPD_C8-Pad2)") (class "Default")
      (node (ref "EPD_C8") (pin "2") (pinfunction "2_2") (pintype "passive"))
      (node (ref "J1") (pin "20") (pinfunction "20_20") (pintype "bidirectional"))
    )
    (net (code "30") (name "Net-(EPD_C10-Pad2)") (class "Default")
      (node (ref "EPD_C10") (pin "2") (pinfunction "2_2") (pintype "passive"))
      (node (ref "J1") (pin "22") (pinfunction "22_22") (pintype "bidirectional"))
    )
    (net (code "31") (name "Net-(EPD_C11-Pad2)") (class "Default")
      (node (ref "EPD_C11") (pin "2") (pinfunction "2_2") (pintype "passive"))
      (node (ref "J1") (pin "23") (pinfunction "23_23") (pintype "bidirectional"))
    )
    (net (code "32") (name "Net-(EPD_C12-Pad2)") (class "Default")
      (node (ref "EPD_C12") (pin "2") (pinfunction "2_2") (pintype "passive"))
      (node (ref "J1") (pin "24") (pinfunction "24_24") (pintype "bidirectional"))
    )
    (net (code "33") (name "Net-(IC1-CT)") (class "Default")
      (node (ref "C_DELAY") (pin "1") (pinfunction "1_1") (pintype "passive"))
      (node (ref "IC1") (pin "5") (pinfunction "CT_5") (pintype "bidirectional"))
    )
    (net (code "34") (name "Net-(J2-PadA5)") (class "Default")
      (node (ref "J2") (pin "A5") (pinfunction "A5_A5") (pintype "bidirectional"))
      (node (ref "R2-USB1") (pin "2") (pinfunction "2_2") (pintype "passive"))
    )
    (net (code "35") (name "Net-(J2-PadB5)") (class "Default")
      (node (ref "J2") (pin "B5") (pinfunction "B5_B5") (pintype "bidirectional"))
      (node (ref "R2-USB") (pin "1") (pinfunction "1_1") (pintype "passive"))
    )
    (net (code "36") (name "Net-(MCP73831-PROG)") (class "Default")
      (node (ref "MCP73831") (pin "5") (pinfunction "PROG_5") (pintype "input"))
      (node (ref "R2_BAT") (pin "2") (pinfunction "2_2") (pintype "passive"))
    )
    (net (code "37") (name "Net-(MCP73831-STAT)") (class "Default")
      (node (ref "MCP73831") (pin "1") (pinfunction "STAT_1") (pintype "output"))
      (node (ref "R1_BAT") (pin "2") (pinfunction "2_2") (pintype "passive"))
    )
    (net (code "38") (name "PREVGH") (class "Default")
      (node (ref "D5") (pin "1") (pinfunction "K_1") (pintype "bidirectional"))
      (node (ref "EPD_C9") (pin "2") (pinfunction "2_2") (pintype "passive"))
      (node (ref "J1") (pin "21") (pinfunction "21_21") (pintype "bidirectional"))
    )
    (net (code "39") (name "PREVGL") (class "Default")
      (node (ref "D4") (pin "2") (pinfunction "A_2") (pintype "bidirectional"))
    )
    (net (code "40") (name "RESE") (class "Default")
      (node (ref "J1") (pin "3") (pinfunction "3_3") (pintype "bidirectional"))
      (node (ref "Q3") (pin "2") (pinfunction "S_2") (pintype "bidirectional"))
      (node (ref "R3") (pin "2") (pinfunction "2_2") (pintype "passive"))
    )
    (net (code "41") (name "RESE'") (class "Default")
      (node (ref "R2") (pin "2") (pinfunction "2_2") (pintype "passive"))
      (node (ref "R3") (pin "1") (pinfunction "1_1") (pintype "passive"))
      (node (ref "SJ1") (pin "2") (pinfunction "2_2") (pintype "passive"))
    )
    (net (code "42") (name "RESET") (class "Default")
      (node (ref "BUT1") (pin "3") (pinfunction "3_3") (pintype "passive"))
      (node (ref "BUT1") (pin "4") (pinfunction "4_4") (pintype "passive"))
      (node (ref "C5") (pin "1") (pinfunction "1_1") (pintype "passive"))
      (node (ref "IC1") (pin "1") (pinfunction "VOUT_1") (pintype "bidirectional"))
      (node (ref "R_RESET") (pin "1") (pinfunction "1_1") (pintype "passive"))
      (node (ref "U2") (pin "3") (pinfunction "EN_3") (pintype "input"))
    )
    (net (code "43") (name "RTC_RST") (class "Default")
      (node (ref "U2") (pin "16") (pinfunction "IO18_16") (pintype "bidirectional"))
      (node (ref "U3") (pin "4") (pinfunction "~{RST}_4") (pintype "input"))
    )
    (net (code "44") (name "RX") (class "Default")
      (node (ref "TP2") (pin "TP") (pinfunction "TP_TP") (pintype "input"))
      (node (ref "U2") (pin "24") (pinfunction "RXD0/GPIO17_24") (pintype "bidirectional"))
    )
    (net (code "45") (name "SCK") (class "Default")
      (node (ref "D10") (pin "2") (pinfunction "2_2") (pintype "passive"))
      (node (ref "J1") (pin "13") (pinfunction "13_13") (pintype "bidirectional"))
      (node (ref "J4") (pin "P5") (pinfunction "CLK_P5") (pintype "bidirectional"))
      (node (ref "R6") (pin "1") (pinfunction "1_1") (pintype "passive"))
      (node (ref "TP8") (pin "TP") (pinfunction "TP_TP") (pintype "input"))
      (node (ref "U1") (pin "6") (pinfunction "CLK_6") (pintype "input"))
      (node (ref "U2") (pin "6") (pinfunction "IO6_6") (pintype "bidirectional"))
    )
    (net (code "46") (name "SCL") (class "Default")
      (node (ref "J3") (pin "4") (pinfunction "4_4") (pintype "passive"))
      (node (ref "R2-PINH") (pin "1") (pinfunction "1_1") (pintype "passive"))
      (node (ref "SENSOR2") (pin "4") (pinfunction "SCK_4") (pintype "input"))
      (node (ref "U2") (pin "20") (pinfunction "IO22_20") (pintype "bidirectional"))
      (node (ref "U3") (pin "16") (pinfunction "SCL_16") (pintype "input"))
      (node (ref "U4") (pin "7") (pinfunction "SCL_7") (pintype "input"))
    )
    (net (code "47") (name "SDA") (class "Default")
      (node (ref "J3") (pin "3") (pinfunction "3_3") (pintype "passive"))
      (node (ref "R1_PINH") (pin "1") (pinfunction "1_1") (pintype "passive"))
      (node (ref "SENSOR2") (pin "3") (pinfunction "SDI_3") (pintype "bidirectional"))
      (node (ref "U2") (pin "19") (pinfunction "IO21_19") (pintype "bidirectional"))
      (node (ref "U3") (pin "15") (pinfunction "SDA_15") (pintype "bidirectional"))
      (node (ref "U4") (pin "8") (pinfunction "SDA_8") (pintype "bidirectional"))
    )
    (net (code "48") (name "SRC") (class "Default")
      (node (ref "C4") (pin "2") (pinfunction "2_2") (pintype "passive"))
      (node (ref "D5") (pin "2") (pinfunction "A_2") (pintype "bidirectional"))
      (node (ref "L1") (pin "1") (pinfunction "1_1") (pintype "passive"))
      (node (ref "Q3") (pin "3") (pinfunction "D_3") (pintype "bidirectional"))
    )
    (net (code "49") (name "SS_SD") (class "Default")
      (node (ref "D8") (pin "2") (pinfunction "2_2") (pintype "passive"))
      (node (ref "J4") (pin "P2") (pinfunction "CD/DAT3_P2") (pintype "bidirectional"))
      (node (ref "R10") (pin "1") (pinfunction "1_1") (pintype "passive"))
      (node (ref "U2") (pin "4") (pinfunction "IO4_4") (pintype "bidirectional"))
    )
    (net (code "50") (name "TX") (class "Default")
      (node (ref "TP1") (pin "TP") (pinfunction "TP_TP") (pintype "input"))
      (node (ref "U2") (pin "25") (pinfunction "TXD0/GPIO16_25") (pintype "bidirectional"))
    )
    (net (code "51") (name "USB_D+") (class "Default")
      (node (ref "D1") (pin "1") (pinfunction "I/O1_1_1") (pintype "bidirectional"))
      (node (ref "U2") (pin "14") (pinfunction "IO13_14") (pintype "bidirectional"))
    )
    (net (code "52") (name "USB_D-") (class "Default")
      (node (ref "D1") (pin "3") (pinfunction "I/O2_1_3") (pintype "bidirectional"))
      (node (ref "U2") (pin "13") (pinfunction "IO12_13") (pintype "bidirectional"))
    )
    (net (code "53") (name "VBAT") (class "Default")
      (node (ref "C2_BAT") (pin "1") (pinfunction "1_1") (pintype "passive"))
      (node (ref "MCP73831") (pin "3") (pinfunction "VBAT_3") (pintype "power_in"))
      (node (ref "Q1") (pin "3") (pinfunction "D_3") (pintype "bidirectional"))
      (node (ref "TP3") (pin "TP") (pinfunction "TP_TP") (pintype "input"))
      (node (ref "U4") (pin "2") (pinfunction "CELL_2") (pintype "power_in"))
      (node (ref "U4") (pin "3") (pinfunction "VDD_3") (pintype "power_in"))
    )
    (net (code "54") (name "VBUS") (class "Default")
      (node (ref "C1_BAT") (pin "1") (pinfunction "1_1") (pintype "passive"))
      (node (ref "C4_USB") (pin "1") (pinfunction "1_1") (pintype "passive"))
      (node (ref "C5_USB") (pin "1") (pinfunction "1_1") (pintype "passive"))
      (node (ref "CHG_LED") (pin "A") (pinfunction "A_A") (pintype "passive"))
      (node (ref "D1") (pin "5") (pinfunction "VBUS_5") (pintype "bidirectional"))
      (node (ref "D2") (pin "2") (pinfunction "ANODE_2") (pintype "bidirectional"))
      (node (ref "MCP73831") (pin "4") (pinfunction "VIN_4") (pintype "power_in"))
      (node (ref "PFMF.050.1") (pin "2") (pinfunction "2_2") (pintype "passive"))
      (node (ref "Q1") (pin "1") (pinfunction "G_1") (pintype "bidirectional"))
      (node (ref "R1_PWRUSB") (pin "2") (pinfunction "2_2") (pintype "passive"))
      (node (ref "TP14") (pin "TP") (pinfunction "TP_TP") (pintype "input"))
    )
    (net (code "55") (name "VRTC") (class "Default")
      (node (ref "C10_SUPERCAP") (pin "2") (pinfunction "2_2") (pintype "passive"))
      (node (ref "C8") (pin "1") (pinfunction "1_1") (pintype "passive"))
      (node (ref "R_CAPACITOR") (pin "2") (pinfunction "2_2") (pintype "passive"))
      (node (ref "U3") (pin "14") (pinfunction "VBAT_14") (pintype "power_in"))
    )
    (net (code "56") (name "VUSB") (class "Default")
      (node (ref "J2") (pin "A4") (pinfunction "A4_A4") (pintype "bidirectional"))
      (node (ref "J2") (pin "A9") (pinfunction "A9_A9") (pintype "bidirectional"))
      (node (ref "J2") (pin "B4") (pinfunction "B4_B4") (pintype "bidirectional"))
      (node (ref "J2") (pin "B9") (pinfunction "B9_B9") (pintype "bidirectional"))
      (node (ref "PFMF.050.1") (pin "1") (pinfunction "1_1") (pintype "passive"))
    )
    (net (code "57") (name "unconnected-(IC1-NC-Pad4)") (class "Default")
      (node (ref "IC1") (pin "4") (pinfunction "NC_4") (pintype "no_connect"))
    )
    (net (code "58") (name "unconnected-(IC4-NC-Pad4)") (class "Default")
      (node (ref "IC4") (pin "4") (pinfunction "NC_4") (pintype "no_connect"))
    )
    (net (code "59") (name "unconnected-(J1-Pad1)") (class "Default")
      (node (ref "J1") (pin "1") (pinfunction "1_1") (pintype "bidirectional"))
    )
    (net (code "60") (name "unconnected-(J1-Pad6)") (class "Default")
      (node (ref "J1") (pin "6") (pinfunction "6_6") (pintype "bidirectional"))
    )
    (net (code "61") (name "unconnected-(J1-Pad7)") (class "Default")
      (node (ref "J1") (pin "7") (pinfunction "7_7") (pintype "bidirectional"))
    )
    (net (code "62") (name "unconnected-(J2-PadA8)") (class "Default")
      (node (ref "J2") (pin "A8") (pinfunction "A8_A8") (pintype "bidirectional"))
    )
    (net (code "63") (name "unconnected-(J2-PadB8)") (class "Default")
      (node (ref "J2") (pin "B8") (pinfunction "B8_B8") (pintype "bidirectional"))
    )
    (net (code "64") (name "unconnected-(J4-DAT1-PadP8)") (class "Default")
      (node (ref "J4") (pin "P8") (pinfunction "DAT1_P8") (pintype "bidirectional"))
    )
    (net (code "65") (name "unconnected-(J4-DAT2-PadP1)") (class "Default")
      (node (ref "J4") (pin "P1") (pinfunction "DAT2_P1") (pintype "bidirectional"))
    )
    (net (code "66") (name "unconnected-(J4-DETECTION_1-PadS1)") (class "Default")
      (node (ref "J4") (pin "S1") (pinfunction "DETECTION_1_S1") (pintype "bidirectional"))
    )
    (net (code "67") (name "unconnected-(J4-DETECTION_2-PadS2)") (class "Default")
      (node (ref "J4") (pin "S2") (pinfunction "DETECTION_2_S2") (pintype "bidirectional"))
    )
    (net (code "68") (name "unconnected-(U2-NC-Pad22)") (class "Default")
      (node (ref "U2") (pin "22") (pinfunction "NC_22") (pintype "no_connect"))
    )
    (net (code "69") (name "unconnected-(U4-~{ALERT}-Pad5)") (class "Default")
      (node (ref "U4") (pin "5") (pinfunction "~{ALERT}_5") (pintype "output"))
    )
  )
)
